# PIC_Zone.net
KiCad netlist of a schematic drawn in Altium Designer
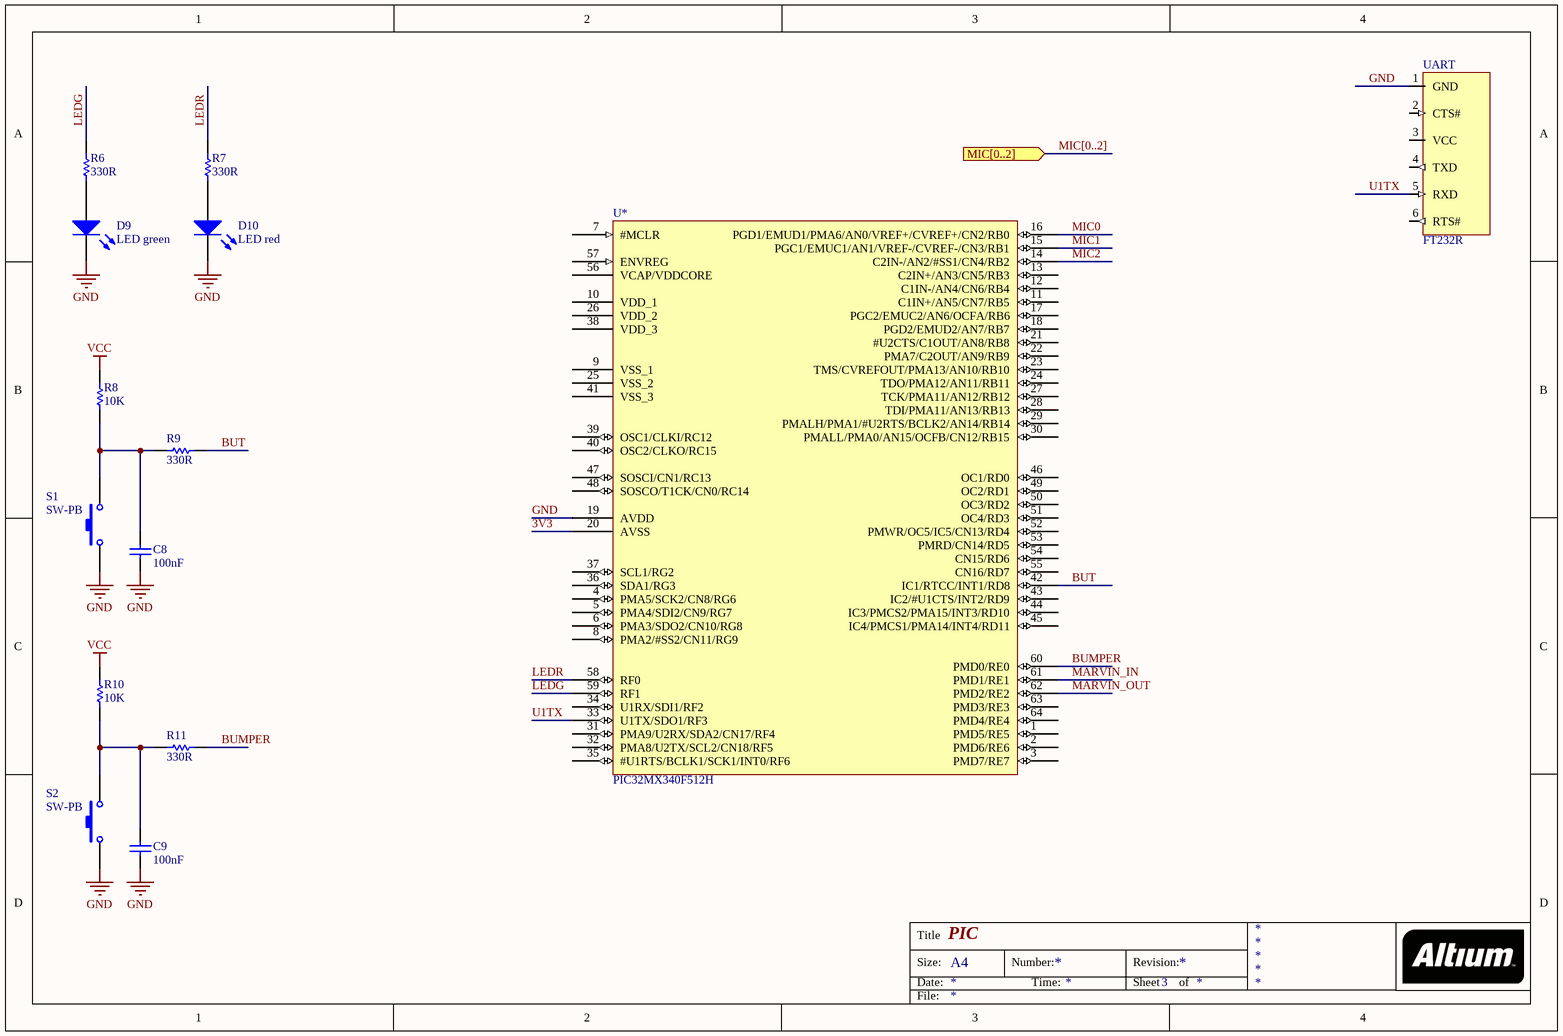
[diagram p0: PIC_Zone.SchDoc]

(export (version "E")
  (design (tool "Eeschema 10.0.6"))
  (components
    (comp (ref "C8")
      (value "100nF")
      (footprint "RAD-0.3")
      (description "Capacitor")
      (fields (field (name "PUBLISHER") "Altium Limited"))
      (libsource (lib "Miscellaneous Devices") (part "Cap"))
    )
    (comp (ref "C9")
      (value "100nF")
      (footprint "RAD-0.3")
      (description "Capacitor")
      (fields (field (name "PUBLISHER") "Altium Limited"))
      (libsource (lib "Miscellaneous Devices") (part "Cap"))
    )
    (comp (ref "D9")
      (value "LED green")
      (footprint "LED-0")
      (description "Typical INFRARED GaAs LED")
      (fields (field (name "PUBLISHER") "Altium Limited"))
      (libsource (lib "Miscellaneous Devices") (part "LED0"))
    )
    (comp (ref "D10")
      (value "LED red")
      (footprint "LED-0")
      (description "Typical INFRARED GaAs LED")
      (fields (field (name "PUBLISHER") "Altium Limited"))
      (libsource (lib "Miscellaneous Devices") (part "LED0"))
    )
    (comp (ref "R6")
      (value "330R")
      (footprint "AXIAL-0.3")
      (description "Resistor")
      (fields (field (name "PUBLISHER") "Altium Limited"))
      (libsource (lib "Miscellaneous Devices") (part "Res1"))
    )
    (comp (ref "R7")
      (value "330R")
      (footprint "AXIAL-0.3")
      (description "Resistor")
      (fields (field (name "PUBLISHER") "Altium Limited"))
      (libsource (lib "Miscellaneous Devices") (part "Res1"))
    )
    (comp (ref "R8")
      (value "10K")
      (footprint "AXIAL-0.3")
      (description "Resistor")
      (fields (field (name "PUBLISHER") "Altium Limited"))
      (libsource (lib "Miscellaneous Devices") (part "Res1"))
    )
    (comp (ref "R9")
      (value "330R")
      (footprint "AXIAL-0.3")
      (description "Resistor")
      (fields (field (name "PUBLISHER") "Altium Limited"))
      (libsource (lib "Miscellaneous Devices") (part "Res1"))
    )
    (comp (ref "R10")
      (value "10K")
      (footprint "AXIAL-0.3")
      (description "Resistor")
      (fields (field (name "PUBLISHER") "Altium Limited"))
      (libsource (lib "Miscellaneous Devices") (part "Res1"))
    )
    (comp (ref "R11")
      (value "330R")
      (footprint "AXIAL-0.3")
      (description "Resistor")
      (fields (field (name "PUBLISHER") "Altium Limited"))
      (libsource (lib "Miscellaneous Devices") (part "Res1"))
    )
    (comp (ref "S1")
      (value "SW-PB")
      (footprint "SPST-2")
      (description "Switch")
      (fields (field (name "PUBLISHER") "Altium Limited"))
      (libsource (lib "Miscellaneous Devices") (part "SW-PB"))
    )
    (comp (ref "S2")
      (value "SW-PB")
      (footprint "SPST-2")
      (description "Switch")
      (fields (field (name "PUBLISHER") "Altium Limited"))
      (libsource (lib "Miscellaneous Devices") (part "SW-PB"))
    )
    (comp (ref "U*") (value "PIC32MX340F512H") (libsource (lib "SCHLIB_Autobot") (part "PIC32MX340F512H")))
    (comp (ref "UART") (value "FT232R") (libsource (lib "SCHLIB_Autobot") (part "FT232R")))
  )
  (nets
    (net (code "1") (name "/3V3") (class "Default")
      (node (ref "U*") (pin "20") (pinfunction "AVSS_20") (pintype "power_in"))
    )
    (net (code "2") (name "/BUMPER") (class "Default")
      (node (ref "R11") (pin "1") (pinfunction "1_1") (pintype "passive"))
      (node (ref "U*") (pin "60") (pinfunction "PMD0/RE0_60") (pintype "bidirectional"))
    )
    (net (code "3") (name "/BUT") (class "Default")
      (node (ref "R9") (pin "1") (pinfunction "1_1") (pintype "passive"))
      (node (ref "U*") (pin "42") (pinfunction "IC1/RTCC/INT1/RD8_42") (pintype "bidirectional"))
    )
    (net (code "4") (name "/LEDG") (class "Default")
      (node (ref "R6") (pin "2") (pinfunction "2_2") (pintype "passive"))
      (node (ref "U*") (pin "59") (pinfunction "RF1_59") (pintype "bidirectional"))
    )
    (net (code "5") (name "/LEDR") (class "Default")
      (node (ref "R7") (pin "2") (pinfunction "2_2") (pintype "passive"))
      (node (ref "U*") (pin "58") (pinfunction "RF0_58") (pintype "bidirectional"))
    )
    (net (code "6") (name "/MARVIN_IN") (class "Default")
      (node (ref "U*") (pin "61") (pinfunction "PMD1/RE1_61") (pintype "bidirectional"))
    )
    (net (code "7") (name "/MARVIN_OUT") (class "Default")
      (node (ref "U*") (pin "62") (pinfunction "PMD2/RE2_62") (pintype "bidirectional"))
    )
    (net (code "8") (name "/MIC0") (class "Default")
      (node (ref "U*") (pin "16") (pinfunction "PGD1/EMUD1/PMA6/AN0/VREF+/CVREF+/CN2/RB0_16") (pintype "bidirectional"))
    )
    (net (code "9") (name "/MIC1") (class "Default")
      (node (ref "U*") (pin "15") (pinfunction "PGC1/EMUC1/AN1/VREF-/CVREF-/CN3/RB1_15") (pintype "bidirectional"))
    )
    (net (code "10") (name "/MIC2") (class "Default")
      (node (ref "U*") (pin "14") (pinfunction "C2IN-/AN2/#SS1/CN4/RB2_14") (pintype "bidirectional"))
    )
    (net (code "12") (name "/U1TX") (class "Default")
      (node (ref "U*") (pin "33") (pinfunction "U1TX/SDO1/RF3_33") (pintype "bidirectional"))
      (node (ref "UART") (pin "5") (pinfunction "RXD_5") (pintype "input"))
    )
    (net (code "13") (name "GND") (class "Default")
      (node (ref "C8") (pin "2") (pinfunction "2_2") (pintype "passive"))
      (node (ref "C9") (pin "2") (pinfunction "2_2") (pintype "passive"))
      (node (ref "D10") (pin "2") (pinfunction "K_2") (pintype "passive"))
      (node (ref "D9") (pin "2") (pinfunction "K_2") (pintype "passive"))
      (node (ref "S1") (pin "1") (pinfunction "1_1") (pintype "passive"))
      (node (ref "S2") (pin "1") (pinfunction "1_1") (pintype "passive"))
      (node (ref "U*") (pin "19") (pinfunction "AVDD_19") (pintype "power_in"))
      (node (ref "UART") (pin "1") (pinfunction "GND_1") (pintype "passive"))
    )
    (net (code "14") (name "Net-(C8-Pad1)") (class "Default")
      (node (ref "C8") (pin "1") (pinfunction "1_1") (pintype "passive"))
      (node (ref "R8") (pin "1") (pinfunction "1_1") (pintype "passive"))
      (node (ref "R9") (pin "2") (pinfunction "2_2") (pintype "passive"))
      (node (ref "S1") (pin "2") (pinfunction "2_2") (pintype "passive"))
    )
    (net (code "15") (name "Net-(C9-Pad1)") (class "Default")
      (node (ref "C9") (pin "1") (pinfunction "1_1") (pintype "passive"))
      (node (ref "R10") (pin "1") (pinfunction "1_1") (pintype "passive"))
      (node (ref "R11") (pin "2") (pinfunction "2_2") (pintype "passive"))
      (node (ref "S2") (pin "2") (pinfunction "2_2") (pintype "passive"))
    )
    (net (code "16") (name "Net-(D9-A)") (class "Default")
      (node (ref "D9") (pin "1") (pinfunction "A_1") (pintype "passive"))
      (node (ref "R6") (pin "1") (pinfunction "1_1") (pintype "passive"))
    )
    (net (code "17") (name "Net-(D10-A)") (class "Default")
      (node (ref "D10") (pin "1") (pinfunction "A_1") (pintype "passive"))
      (node (ref "R7") (pin "1") (pinfunction "1_1") (pintype "passive"))
    )
    (net (code "18") (name "VCC") (class "Default")
      (node (ref "R10") (pin "2") (pinfunction "2_2") (pintype "passive"))
      (node (ref "R8") (pin "2") (pinfunction "2_2") (pintype "passive"))
    )
    (net (code "19") (name "unconnected-(U*-#MCLR-Pad7)") (class "Default")
      (node (ref "U*") (pin "7") (pinfunction "#MCLR_7") (pintype "input"))
    )
    (net (code "20") (name "unconnected-(U*-#U1RTS{slash}BCLK1{slash}SCK1{slash}INT0{slash}RF6-Pad35)") (class "Default")
      (node (ref "U*") (pin "35") (pinfunction "#U1RTS/BCLK1/SCK1/INT0/RF6_35") (pintype "bidirectional"))
    )
    (net (code "21") (name "unconnected-(U*-#U2CTS{slash}C1OUT{slash}AN8{slash}RB8-Pad21)") (class "Default")
      (node (ref "U*") (pin "21") (pinfunction "#U2CTS/C1OUT/AN8/RB8_21") (pintype "bidirectional"))
    )
    (net (code "22") (name "unconnected-(U*-C1IN+{slash}AN5{slash}CN7{slash}RB5-Pad11)") (class "Default")
      (node (ref "U*") (pin "11") (pinfunction "C1IN+/AN5/CN7/RB5_11") (pintype "bidirectional"))
    )
    (net (code "23") (name "unconnected-(U*-C1IN-{slash}AN4{slash}CN6{slash}RB4-Pad12)") (class "Default")
      (node (ref "U*") (pin "12") (pinfunction "C1IN-/AN4/CN6/RB4_12") (pintype "bidirectional"))
    )
    (net (code "24") (name "unconnected-(U*-C2IN+{slash}AN3{slash}CN5{slash}RB3-Pad13)") (class "Default")
      (node (ref "U*") (pin "13") (pinfunction "C2IN+/AN3/CN5/RB3_13") (pintype "bidirectional"))
    )
    (net (code "25") (name "unconnected-(U*-CN15{slash}RD6-Pad54)") (class "Default")
      (node (ref "U*") (pin "54") (pinfunction "CN15/RD6_54") (pintype "bidirectional"))
    )
    (net (code "26") (name "unconnected-(U*-CN16{slash}RD7-Pad55)") (class "Default")
      (node (ref "U*") (pin "55") (pinfunction "CN16/RD7_55") (pintype "bidirectional"))
    )
    (net (code "27") (name "unconnected-(U*-ENVREG-Pad57)") (class "Default")
      (node (ref "U*") (pin "57") (pinfunction "ENVREG_57") (pintype "input"))
    )
    (net (code "28") (name "unconnected-(U*-IC2{slash}#U1CTS{slash}INT2{slash}RD9-Pad43)") (class "Default")
      (node (ref "U*") (pin "43") (pinfunction "IC2/#U1CTS/INT2/RD9_43") (pintype "bidirectional"))
    )
    (net (code "29") (name "unconnected-(U*-IC3{slash}PMCS2{slash}PMA15{slash}INT3{slash}RD10-Pad44)") (class "Default")
      (node (ref "U*") (pin "44") (pinfunction "IC3/PMCS2/PMA15/INT3/RD10_44") (pintype "bidirectional"))
    )
    (net (code "30") (name "unconnected-(U*-IC4{slash}PMCS1{slash}PMA14{slash}INT4{slash}RD11-Pad45)") (class "Default")
      (node (ref "U*") (pin "45") (pinfunction "IC4/PMCS1/PMA14/INT4/RD11_45") (pintype "bidirectional"))
    )
    (net (code "31") (name "unconnected-(U*-OC1{slash}RD0-Pad46)") (class "Default")
      (node (ref "U*") (pin "46") (pinfunction "OC1/RD0_46") (pintype "bidirectional"))
    )
    (net (code "32") (name "unconnected-(U*-OC2{slash}RD1-Pad49)") (class "Default")
      (node (ref "U*") (pin "49") (pinfunction "OC2/RD1_49") (pintype "bidirectional"))
    )
    (net (code "33") (name "unconnected-(U*-OC3{slash}RD2-Pad50)") (class "Default")
      (node (ref "U*") (pin "50") (pinfunction "OC3/RD2_50") (pintype "bidirectional"))
    )
    (net (code "34") (name "unconnected-(U*-OC4{slash}RD3-Pad51)") (class "Default")
      (node (ref "U*") (pin "51") (pinfunction "OC4/RD3_51") (pintype "bidirectional"))
    )
    (net (code "35") (name "unconnected-(U*-OSC1{slash}CLKI{slash}RC12-Pad39)") (class "Default")
      (node (ref "U*") (pin "39") (pinfunction "OSC1/CLKI/RC12_39") (pintype "bidirectional"))
    )
    (net (code "36") (name "unconnected-(U*-OSC2{slash}CLKO{slash}RC15-Pad40)") (class "Default")
      (node (ref "U*") (pin "40") (pinfunction "OSC2/CLKO/RC15_40") (pintype "bidirectional"))
    )
    (net (code "37") (name "unconnected-(U*-PGC2{slash}EMUC2{slash}AN6{slash}OCFA{slash}RB6-Pad17)") (class "Default")
      (node (ref "U*") (pin "17") (pinfunction "PGC2/EMUC2/AN6/OCFA/RB6_17") (pintype "bidirectional"))
    )
    (net (code "38") (name "unconnected-(U*-PGD2{slash}EMUD2{slash}AN7{slash}RB7-Pad18)") (class "Default")
      (node (ref "U*") (pin "18") (pinfunction "PGD2/EMUD2/AN7/RB7_18") (pintype "bidirectional"))
    )
    (net (code "39") (name "unconnected-(U*-PMA2{slash}#SS2{slash}CN11{slash}RG9-Pad8)") (class "Default")
      (node (ref "U*") (pin "8") (pinfunction "PMA2/#SS2/CN11/RG9_8") (pintype "bidirectional"))
    )
    (net (code "40") (name "unconnected-(U*-PMA3{slash}SDO2{slash}CN10{slash}RG8-Pad6)") (class "Default")
      (node (ref "U*") (pin "6") (pinfunction "PMA3/SDO2/CN10/RG8_6") (pintype "bidirectional"))
    )
    (net (code "41") (name "unconnected-(U*-PMA4{slash}SDI2{slash}CN9{slash}RG7-Pad5)") (class "Default")
      (node (ref "U*") (pin "5") (pinfunction "PMA4/SDI2/CN9/RG7_5") (pintype "bidirectional"))
    )
    (net (code "42") (name "unconnected-(U*-PMA5{slash}SCK2{slash}CN8{slash}RG6-Pad4)") (class "Default")
      (node (ref "U*") (pin "4") (pinfunction "PMA5/SCK2/CN8/RG6_4") (pintype "bidirectional"))
    )
    (net (code "43") (name "unconnected-(U*-PMA7{slash}C2OUT{slash}AN9{slash}RB9-Pad22)") (class "Default")
      (node (ref "U*") (pin "22") (pinfunction "PMA7/C2OUT/AN9/RB9_22") (pintype "bidirectional"))
    )
    (net (code "44") (name "unconnected-(U*-PMA8{slash}U2TX{slash}SCL2{slash}CN18{slash}RF5-Pad32)") (class "Default")
      (node (ref "U*") (pin "32") (pinfunction "PMA8/U2TX/SCL2/CN18/RF5_32") (pintype "bidirectional"))
    )
    (net (code "45") (name "unconnected-(U*-PMA9{slash}U2RX{slash}SDA2{slash}CN17{slash}RF4-Pad31)") (class "Default")
      (node (ref "U*") (pin "31") (pinfunction "PMA9/U2RX/SDA2/CN17/RF4_31") (pintype "bidirectional"))
    )
    (net (code "46") (name "unconnected-(U*-PMALH{slash}PMA1{slash}#U2RTS{slash}BCLK2{slash}AN14{slash}RB14-Pad29)") (class "Default")
      (node (ref "U*") (pin "29") (pinfunction "PMALH/PMA1/#U2RTS/BCLK2/AN14/RB14_29") (pintype "bidirectional"))
    )
    (net (code "47") (name "unconnected-(U*-PMALL{slash}PMA0{slash}AN15{slash}OCFB{slash}CN12{slash}RB15-Pad30)") (class "Default")
      (node (ref "U*") (pin "30") (pinfunction "PMALL/PMA0/AN15/OCFB/CN12/RB15_30") (pintype "bidirectional"))
    )
    (net (code "48") (name "unconnected-(U*-PMD3{slash}RE3-Pad63)") (class "Default")
      (node (ref "U*") (pin "63") (pinfunction "PMD3/RE3_63") (pintype "bidirectional"))
    )
    (net (code "49") (name "unconnected-(U*-PMD4{slash}RE4-Pad64)") (class "Default")
      (node (ref "U*") (pin "64") (pinfunction "PMD4/RE4_64") (pintype "bidirectional"))
    )
    (net (code "50") (name "unconnected-(U*-PMD5{slash}RE5-Pad1)") (class "Default")
      (node (ref "U*") (pin "1") (pinfunction "PMD5/RE5_1") (pintype "bidirectional"))
    )
    (net (code "51") (name "unconnected-(U*-PMD6{slash}RE6-Pad2)") (class "Default")
      (node (ref "U*") (pin "2") (pinfunction "PMD6/RE6_2") (pintype "bidirectional"))
    )
    (net (code "52") (name "unconnected-(U*-PMD7{slash}RE7-Pad3)") (class "Default")
      (node (ref "U*") (pin "3") (pinfunction "PMD7/RE7_3") (pintype "bidirectional"))
    )
    (net (code "53") (name "unconnected-(U*-PMRD{slash}CN14{slash}RD5-Pad53)") (class "Default")
      (node (ref "U*") (pin "53") (pinfunction "PMRD/CN14/RD5_53") (pintype "bidirectional"))
    )
    (net (code "54") (name "unconnected-(U*-PMWR{slash}OC5{slash}IC5{slash}CN13{slash}RD4-Pad52)") (class "Default")
      (node (ref "U*") (pin "52") (pinfunction "PMWR/OC5/IC5/CN13/RD4_52") (pintype "bidirectional"))
    )
    (net (code "55") (name "unconnected-(U*-SCL1{slash}RG2-Pad37)") (class "Default")
      (node (ref "U*") (pin "37") (pinfunction "SCL1/RG2_37") (pintype "bidirectional"))
    )
    (net (code "56") (name "unconnected-(U*-SDA1{slash}RG3-Pad36)") (class "Default")
      (node (ref "U*") (pin "36") (pinfunction "SDA1/RG3_36") (pintype "bidirectional"))
    )
    (net (code "57") (name "unconnected-(U*-SOSCI{slash}CN1{slash}RC13-Pad47)") (class "Default")
      (node (ref "U*") (pin "47") (pinfunction "SOSCI/CN1/RC13_47") (pintype "bidirectional"))
    )
    (net (code "58") (name "unconnected-(U*-SOSCO{slash}T1CK{slash}CN0{slash}RC14-Pad48)") (class "Default")
      (node (ref "U*") (pin "48") (pinfunction "SOSCO/T1CK/CN0/RC14_48") (pintype "bidirectional"))
    )
    (net (code "59") (name "unconnected-(U*-TCK{slash}PMA11{slash}AN12{slash}RB12-Pad27)") (class "Default")
      (node (ref "U*") (pin "27") (pinfunction "TCK/PMA11/AN12/RB12_27") (pintype "bidirectional"))
    )
    (net (code "60") (name "unconnected-(U*-TDI{slash}PMA11{slash}AN13{slash}RB13-Pad28)") (class "Default")
      (node (ref "U*") (pin "28") (pinfunction "TDI/PMA11/AN13/RB13_28") (pintype "bidirectional"))
    )
    (net (code "61") (name "unconnected-(U*-TDO{slash}PMA12{slash}AN11{slash}RB11-Pad24)") (class "Default")
      (node (ref "U*") (pin "24") (pinfunction "TDO/PMA12/AN11/RB11_24") (pintype "bidirectional"))
    )
    (net (code "62") (name "unconnected-(U*-TMS{slash}CVREFOUT{slash}PMA13{slash}AN10{slash}RB10-Pad23)") (class "Default")
      (node (ref "U*") (pin "23") (pinfunction "TMS/CVREFOUT/PMA13/AN10/RB10_23") (pintype "bidirectional"))
    )
    (net (code "63") (name "unconnected-(U*-U1RX{slash}SDI1{slash}RF2-Pad34)") (class "Default")
      (node (ref "U*") (pin "34") (pinfunction "U1RX/SDI1/RF2_34") (pintype "bidirectional"))
    )
    (net (code "64") (name "unconnected-(U*-VCAP{slash}VDDCORE-Pad56)") (class "Default")
      (node (ref "U*") (pin "56") (pinfunction "VCAP/VDDCORE_56") (pintype "power_in"))
    )
    (net (code "65") (name "unconnected-(U*-VDD_1-Pad10)") (class "Default")
      (node (ref "U*") (pin "10") (pinfunction "VDD_1_10") (pintype "power_in"))
    )
    (net (code "66") (name "unconnected-(U*-VDD_2-Pad26)") (class "Default")
      (node (ref "U*") (pin "26") (pinfunction "VDD_2_26") (pintype "power_in"))
    )
    (net (code "67") (name "unconnected-(U*-VDD_3-Pad38)") (class "Default")
      (node (ref "U*") (pin "38") (pinfunction "VDD_3_38") (pintype "power_in"))
    )
    (net (code "68") (name "unconnected-(U*-VSS_1-Pad9)") (class "Default")
      (node (ref "U*") (pin "9") (pinfunction "VSS_1_9") (pintype "power_in"))
    )
    (net (code "69") (name "unconnected-(U*-VSS_2-Pad25)") (class "Default")
      (node (ref "U*") (pin "25") (pinfunction "VSS_2_25") (pintype "power_in"))
    )
    (net (code "70") (name "unconnected-(U*-VSS_3-Pad41)") (class "Default")
      (node (ref "U*") (pin "41") (pinfunction "VSS_3_41") (pintype "power_in"))
    )
    (net (code "71") (name "unconnected-(UART-CTS#-Pad2)") (class "Default")
      (node (ref "UART") (pin "2") (pinfunction "CTS#_2") (pintype "input"))
    )
    (net (code "72") (name "unconnected-(UART-RTS#-Pad6)") (class "Default")
      (node (ref "UART") (pin "6") (pinfunction "RTS#_6") (pintype "output"))
    )
    (net (code "73") (name "unconnected-(UART-TXD-Pad4)") (class "Default")
      (node (ref "UART") (pin "4") (pinfunction "TXD_4") (pintype "output"))
    )
    (net (code "74") (name "unconnected-(UART-VCC-Pad3)") (class "Default")
      (node (ref "UART") (pin "3") (pinfunction "VCC_3") (pintype "power_in"))
    )
  )
)
